# homeweather.net
KiCad netlist of a schematic drawn in EAGLE
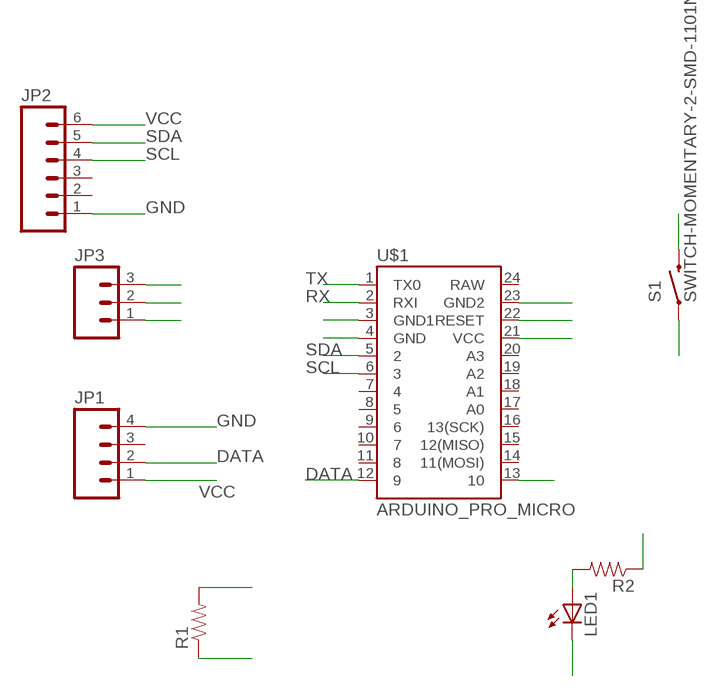
[diagram p0: schematic, sheet 1]

(export (version "E")
  (design (tool "Eeschema 10.0.6"))
  (components
    (comp (ref "JP1")
      (value "M04PTH")
      (footprint "eagle-import:1X04")
      (libsource (lib "eagle-import") (part "M04PTH"))
    )
    (comp (ref "JP2")
      (value "M06SIP")
      (footprint "eagle-import:1X06")
      (libsource (lib "eagle-import") (part "M06SIP"))
    )
    (comp (ref "JP3")
      (value "M03PTH")
      (footprint "eagle-import:1X03")
      (libsource (lib "eagle-import") (part "M03PTH"))
    )
    (comp (ref "LED1")
      (value "LED3MM")
      (footprint "eagle-import:LED3MM")
      (libsource (lib "eagle-import") (part "LED3MM"))
    )
    (comp (ref "R1")
      (value "RESISTOR0805-RES")
      (footprint "eagle-import:0805")
      (libsource (lib "eagle-import") (part "RESISTOR0805-RES"))
    )
    (comp (ref "R2")
      (value "RESISTOR0805-RES")
      (footprint "eagle-import:0805")
      (libsource (lib "eagle-import") (part "RESISTOR0805-RES"))
    )
    (comp (ref "S1")
      (value "SWITCH-MOMENTARY-2-SMD-1101NE")
      (footprint "eagle-import:TACTILE-SWITCH-1101NE")
      (libsource (lib "eagle-import") (part "SWITCH-MOMENTARY-2-SMD-1101NE"))
    )
    (comp (ref "U$1")
      (value "ARDUINO_PRO_MICRO")
      (footprint "eagle-import:ARDUINO_PRO_MICRO")
      (libsource (lib "eagle-import") (part "ARDUINO_PRO_MICRO"))
    )
  )
  (nets
    (net (code "1") (name "/DATA") (class "Default")
      (node (ref "JP1") (pin "2") (pinfunction "2_2") (pintype "passive"))
      (node (ref "R1") (pin "2") (pinfunction "2_2") (pintype "passive"))
      (node (ref "U$1") (pin "12") (pinfunction "9_12") (pintype "bidirectional"))
    )
    (net (code "2") (name "/GND") (class "Default")
      (node (ref "JP1") (pin "4") (pinfunction "4_4") (pintype "passive"))
      (node (ref "JP2") (pin "1") (pinfunction "1_1") (pintype "passive"))
      (node (ref "JP3") (pin "1") (pinfunction "1_1") (pintype "passive"))
      (node (ref "LED1") (pin "K") (pinfunction "C_K") (pintype "passive"))
      (node (ref "S1") (pin "P$1") (pinfunction "1_P$1") (pintype "passive"))
      (node (ref "U$1") (pin "23") (pinfunction "GND2_23") (pintype "bidirectional"))
      (node (ref "U$1") (pin "3") (pinfunction "GND1_3") (pintype "bidirectional"))
      (node (ref "U$1") (pin "4") (pinfunction "GND_4") (pintype "bidirectional"))
    )
    (net (code "3") (name "/LED1") (class "Default")
      (node (ref "R2") (pin "1") (pinfunction "1_1") (pintype "passive"))
      (node (ref "U$1") (pin "13") (pinfunction "10_13") (pintype "bidirectional"))
    )
    (net (code "4") (name "/RESET") (class "Default")
      (node (ref "S1") (pin "P$2") (pinfunction "2_P$2") (pintype "passive"))
      (node (ref "U$1") (pin "22") (pinfunction "RESET_22") (pintype "bidirectional"))
    )
    (net (code "5") (name "/RX") (class "Default")
      (node (ref "JP3") (pin "2") (pinfunction "2_2") (pintype "passive"))
      (node (ref "U$1") (pin "2") (pinfunction "RXI_2") (pintype "bidirectional"))
    )
    (net (code "6") (name "/SCL") (class "Default")
      (node (ref "JP2") (pin "4") (pinfunction "4_4") (pintype "passive"))
      (node (ref "U$1") (pin "6") (pinfunction "3_6") (pintype "bidirectional"))
    )
    (net (code "7") (name "/SDA") (class "Default")
      (node (ref "JP2") (pin "5") (pinfunction "5_5") (pintype "passive"))
      (node (ref "U$1") (pin "5") (pinfunction "2_5") (pintype "bidirectional"))
    )
    (net (code "8") (name "/TX") (class "Default")
      (node (ref "JP3") (pin "3") (pinfunction "3_3") (pintype "passive"))
      (node (ref "U$1") (pin "1") (pinfunction "TX0_1") (pintype "bidirectional"))
    )
    (net (code "9") (name "/VCC") (class "Default")
      (node (ref "JP1") (pin "1") (pinfunction "1_1") (pintype "passive"))
      (node (ref "JP2") (pin "6") (pinfunction "6_6") (pintype "passive"))
      (node (ref "R1") (pin "1") (pinfunction "1_1") (pintype "passive"))
      (node (ref "U$1") (pin "21") (pinfunction "VCC_21") (pintype "bidirectional"))
    )
    (net (code "10") (name "Net-(LED1-PadA)") (class "Default")
      (node (ref "LED1") (pin "A") (pinfunction "A_A") (pintype "passive"))
      (node (ref "R2") (pin "2") (pinfunction "2_2") (pintype "passive"))
    )
    (net (code "11") (name "unconnected-(JP1-Pad3)") (class "Default")
      (node (ref "JP1") (pin "3") (pinfunction "3_3") (pintype "passive"))
    )
    (net (code "12") (name "unconnected-(JP2-Pad2)") (class "Default")
      (node (ref "JP2") (pin "2") (pinfunction "2_2") (pintype "passive"))
    )
    (net (code "13") (name "unconnected-(JP2-Pad3)") (class "Default")
      (node (ref "JP2") (pin "3") (pinfunction "3_3") (pintype "passive"))
    )
    (net (code "14") (name "unconnected-(U$1-4-Pad7)") (class "Default")
      (node (ref "U$1") (pin "7") (pinfunction "4_7") (pintype "bidirectional"))
    )
    (net (code "15") (name "unconnected-(U$1-5-Pad8)") (class "Default")
      (node (ref "U$1") (pin "8") (pinfunction "5_8") (pintype "bidirectional"))
    )
    (net (code "16") (name "unconnected-(U$1-6-Pad9)") (class "Default")
      (node (ref "U$1") (pin "9") (pinfunction "6_9") (pintype "bidirectional"))
    )
    (net (code "17") (name "unconnected-(U$1-7-Pad10)") (class "Default")
      (node (ref "U$1") (pin "10") (pinfunction "7_10") (pintype "bidirectional"))
    )
    (net (code "18") (name "unconnected-(U$1-8-Pad11)") (class "Default")
      (node (ref "U$1") (pin "11") (pinfunction "8_11") (pintype "bidirectional"))
    )
    (net (code "19") (name "unconnected-(U$1-11(MOSI)-Pad14)") (class "Default")
      (node (ref "U$1") (pin "14") (pinfunction "11(MOSI)_14") (pintype "bidirectional"))
    )
    (net (code "20") (name "unconnected-(U$1-12(MISO)-Pad15)") (class "Default")
      (node (ref "U$1") (pin "15") (pinfunction "12(MISO)_15") (pintype "bidirectional"))
    )
    (net (code "21") (name "unconnected-(U$1-13(SCK)-Pad16)") (class "Default")
      (node (ref "U$1") (pin "16") (pinfunction "13(SCK)_16") (pintype "bidirectional"))
    )
    (net (code "22") (name "unconnected-(U$1-A0-Pad17)") (class "Default")
      (node (ref "U$1") (pin "17") (pinfunction "A0_17") (pintype "bidirectional"))
    )
    (net (code "23") (name "unconnected-(U$1-A1-Pad18)") (class "Default")
      (node (ref "U$1") (pin "18") (pinfunction "A1_18") (pintype "bidirectional"))
    )
    (net (code "24") (name "unconnected-(U$1-A2-Pad19)") (class "Default")
      (node (ref "U$1") (pin "19") (pinfunction "A2_19") (pintype "bidirectional"))
    )
    (net (code "25") (name "unconnected-(U$1-A3-Pad20)") (class "Default")
      (node (ref "U$1") (pin "20") (pinfunction "A3_20") (pintype "bidirectional"))
    )
    (net (code "26") (name "unconnected-(U$1-RAW-Pad24)") (class "Default")
      (node (ref "U$1") (pin "24") (pinfunction "RAW_24") (pintype "bidirectional"))
    )
  )
)
